# Schematic.net
KiCad netlist of a schematic drawn in EasyEDA
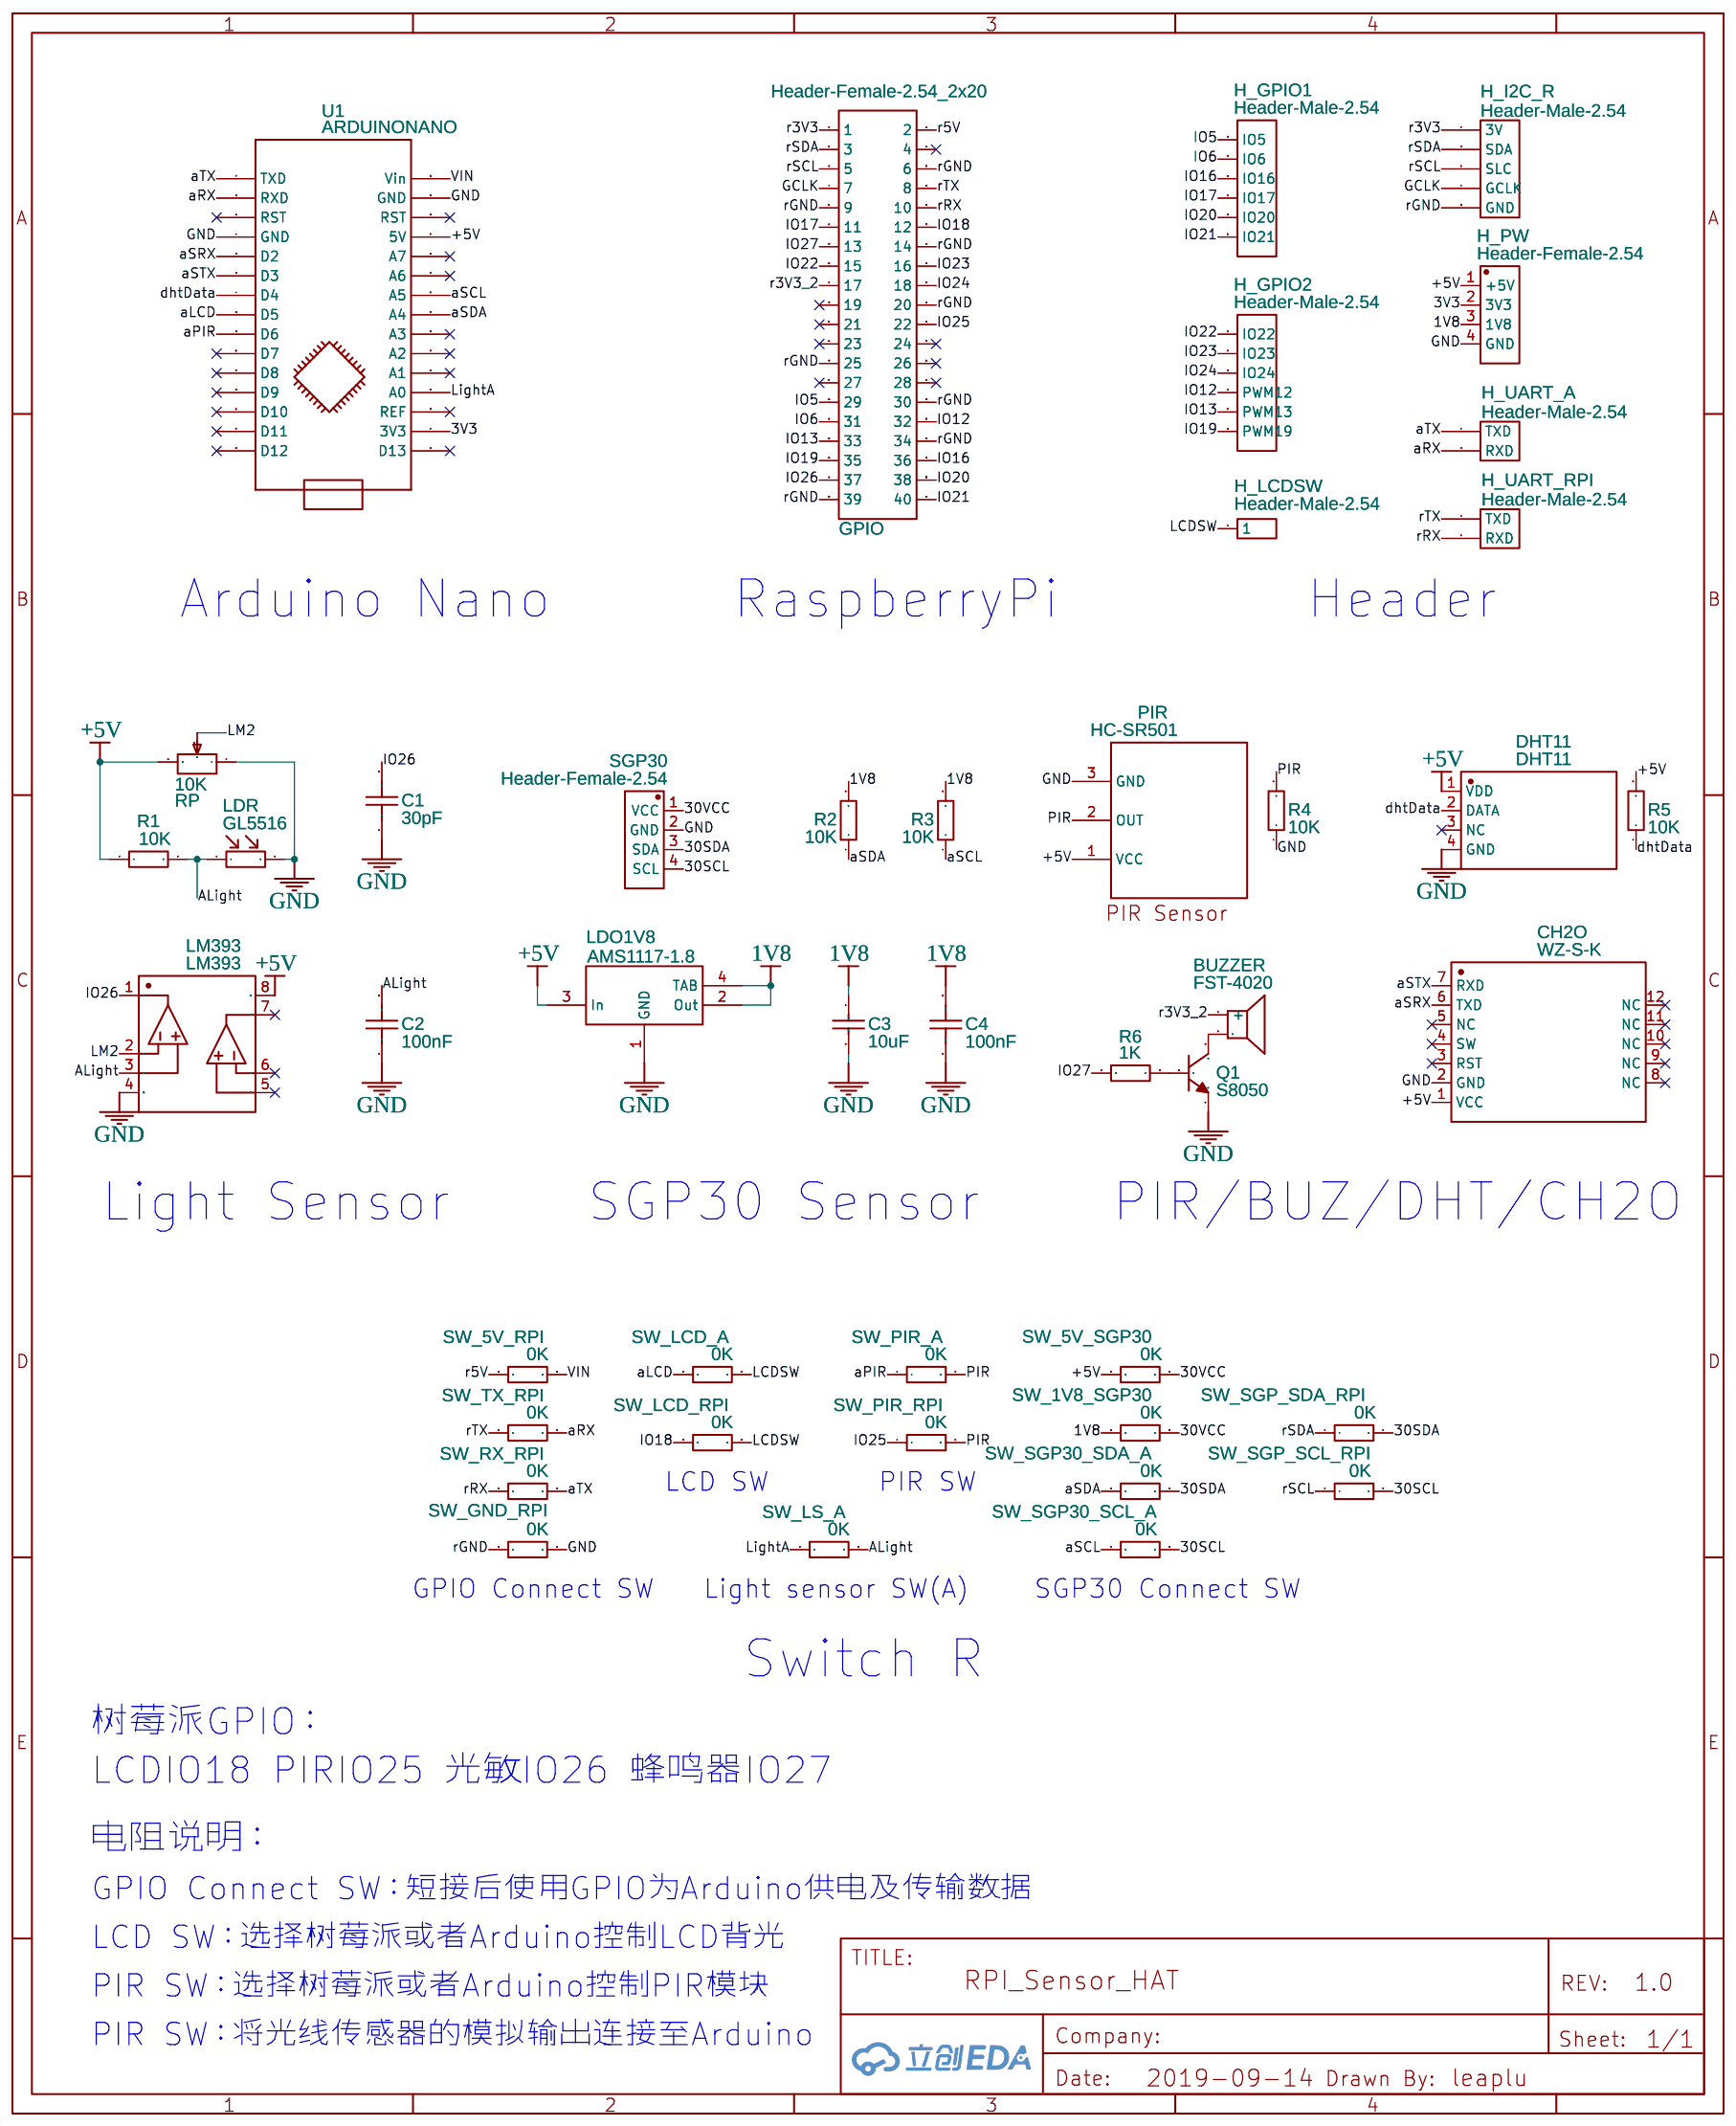
[diagram p0: schematic sheet]

(export (version "E")
  (design (tool "Eeschema 10.0.6"))
  (components
    (comp (ref "BUZZER")
      (value "FST-4020")
      (fields (field (name "BOM_Supplier Part") "C391027"))
      (libsource (lib "") (part "FST-4020"))
    )
    (comp (ref "C1")
      (value "30pF")
      (fields
        (field (name "BOM_Manufacturer Part") "CC0603GRNPO9BN300")
        (field (name "BOM_Supplier Part") "C327012")
      )
      (libsource (lib "") (part "CC0603GRNPO9BN300"))
    )
    (comp (ref "C2")
      (value "100nF")
      (fields
        (field (name "BOM_Manufacturer Part") "CC0603KRX7R0BB104")
        (field (name "BOM_Supplier Part") "C113803")
      )
      (libsource (lib "") (part "CC0603KRX7R0BB104"))
    )
    (comp (ref "C3")
      (value "10uF")
      (fields
        (field (name "BOM_Manufacturer Part") "CC0603KRX5R5BB106")
        (field (name "BOM_Supplier Part") "C109455")
      )
      (libsource (lib "") (part "CC0603KRX5R5BB106"))
    )
    (comp (ref "C4")
      (value "100nF")
      (fields
        (field (name "BOM_Manufacturer Part") "CC0603KRX7R0BB104")
        (field (name "BOM_Supplier Part") "C113803")
      )
      (libsource (lib "") (part "CC0603KRX7R0BB104"))
    )
    (comp (ref "CH2O") (value "WZ-S-K") (libsource (lib "") (part "Unknown_790_530")))
    (comp (ref "DHT11")
      (value "DHT11")
      (fields (field (name "BOM_Supplier Part") "C117051"))
      (libsource (lib "") (part "Unknown_780_415"))
    )
    (comp (ref "GPIO")
      (value "Header-Female-2.54_2x20")
      (fields
        (field (name "BOM_Manufacturer Part") "2.54mm 2*20PFemale header")
        (field (name "BOM_Supplier Part") "C50982")
      )
      (libsource (lib "") (part "Unknown_445_160"))
    )
    (comp (ref "H_GPIO1")
      (value "Header-Male-2.54")
      (fields
        (field (name "BOM_Manufacturer Part") "Header-Male-2.54_1x6")
        (field (name "BOM_Supplier Part") "C37208")
      )
      (libsource (lib "") (part "Header-Male-2.54_1x6_1"))
    )
    (comp (ref "H_GPIO2")
      (value "Header-Male-2.54")
      (fields
        (field (name "BOM_Manufacturer Part") "Header-Male-2.54_1x6")
        (field (name "BOM_Supplier Part") "C37208")
      )
      (libsource (lib "") (part "Header-Male-2.54_1x6"))
    )
    (comp (ref "H_I2C_R")
      (value "Header-Male-2.54")
      (fields
        (field (name "BOM_Manufacturer Part") "2.54mm 1*5P Header")
        (field (name "BOM_Supplier Part") "C50951")
      )
      (libsource (lib "") (part "Unknown_755_80"))
    )
    (comp (ref "H_LCDSW")
      (value "Header-Male-2.54")
      (fields
        (field (name "BOM_Manufacturer Part") "Header-Male-2.54_1x1")
        (field (name "BOM_Supplier Part") "C81276")
      )
      (libsource (lib "") (part "Header-Male-2.54_1x1"))
    )
    (comp (ref "H_PW")
      (value "Header-Female-2.54")
      (fields
        (field (name "BOM_Manufacturer Part") "Headers  Pins 1*4P")
        (field (name "BOM_Supplier Part") "C59481")
      )
      (libsource (lib "") (part "Unknown_760_155"))
    )
    (comp (ref "H_UART_A")
      (value "Header-Male-2.54")
      (fields
        (field (name "BOM_Manufacturer Part") "2.54mm 1*2P")
        (field (name "BOM_Supplier Part") "C36717")
      )
      (libsource (lib "") (part "Unknown_755_220"))
    )
    (comp (ref "H_UART_RPI")
      (value "Header-Male-2.54")
      (fields
        (field (name "BOM_Manufacturer Part") "2.54mm 1*2P")
        (field (name "BOM_Supplier Part") "C36717")
      )
      (libsource (lib "") (part "Unknown_755_265"))
    )
    (comp (ref "LDO1V8")
      (value "AMS1117-1.8")
      (fields (field (name "BOM_Supplier Part") "C6185"))
      (libsource (lib "") (part "Unknown_325_515"))
    )
    (comp (ref "LDR")
      (value "GL5516")
      (fields (field (name "BOM_Supplier Part") "C125626"))
      (libsource (lib "") (part "GL5516"))
    )
    (comp (ref "LM393")
      (value "LM393")
      (fields (field (name "BOM_Supplier Part") "C351428"))
      (libsource (lib "") (part "Unknown_95_525"))
    )
    (comp (ref "PIR") (value "HC-SR501") (libsource (lib "") (part "Unknown_605_415")))
    (comp (ref "Q1")
      (value "S8050")
      (fields (field (name "BOM_Supplier Part") "C181158"))
      (libsource (lib "") (part "Unknown_605_545"))
    )
    (comp (ref "R1")
      (value "10K")
      (fields
        (field (name "BOM_Manufacturer Part") "0603WAF1002T5E")
        (field (name "BOM_Supplier Part") "C25804")
      )
      (libsource (lib "") (part "RMC060310K5%N_4"))
    )
    (comp (ref "R2")
      (value "10K")
      (fields
        (field (name "BOM_Manufacturer Part") "0603WAF1002T5E")
        (field (name "BOM_Supplier Part") "C25804")
      )
      (libsource (lib "") (part "RMC060310K5%N_3"))
    )
    (comp (ref "R3")
      (value "10K")
      (fields
        (field (name "BOM_Manufacturer Part") "0603WAF1002T5E")
        (field (name "BOM_Supplier Part") "C25804")
      )
      (libsource (lib "") (part "RMC060310K5%N_3"))
    )
    (comp (ref "R4")
      (value "10K")
      (fields
        (field (name "BOM_Manufacturer Part") "0603WAF1002T5E")
        (field (name "BOM_Supplier Part") "C25804")
      )
      (libsource (lib "") (part "RMC060310K5%N_3"))
    )
    (comp (ref "R5")
      (value "10K")
      (fields
        (field (name "BOM_Manufacturer Part") "0603WAF1002T5E")
        (field (name "BOM_Supplier Part") "C25804")
      )
      (libsource (lib "") (part "RMC060310K5%N_3"))
    )
    (comp (ref "R6")
      (value "1K")
      (fields
        (field (name "BOM_Manufacturer Part") "RMC06031K5%N")
        (field (name "BOM_Supplier Part") "C269685")
      )
      (libsource (lib "") (part "RMC06031K5%N"))
    )
    (comp (ref "RP")
      (value "10K")
      (fields (field (name "BOM_Manufacturer Part") "3362P-1-103") (field (name "BOM_Supplier Part") "C5047"))
      (libsource (lib "") (part "3362P-1-103"))
    )
    (comp (ref "SGP30")
      (value "Header-Female-2.54")
      (fields
        (field (name "BOM_Manufacturer Part") "Headers  Pins 1*4P")
        (field (name "BOM_Supplier Part") "C59481")
      )
      (libsource (lib "") (part "Unknown_330_425"))
    )
    (comp (ref "SW_1V8_SGP30")
      (value "0K")
      (fields
        (field (name "BOM_Manufacturer Part") "0603WAF1002T5E")
        (field (name "BOM_Supplier Part") "C25804")
      )
      (libsource (lib "") (part "RMC060310K5%N_2"))
    )
    (comp (ref "SW_5V_RPI")
      (value "0K")
      (fields
        (field (name "BOM_Manufacturer Part") "0603WAF5101T5E")
        (field (name "BOM_Supplier Part") "C23186")
      )
      (libsource (lib "") (part "RMC06035.1K5%N_3"))
    )
    (comp (ref "SW_5V_SGP30")
      (value "0K")
      (fields
        (field (name "BOM_Manufacturer Part") "0603WAF1002T5E")
        (field (name "BOM_Supplier Part") "C25804")
      )
      (libsource (lib "") (part "RMC060310K5%N_6"))
    )
    (comp (ref "SW_GND_RPI")
      (value "0K")
      (fields
        (field (name "BOM_Manufacturer Part") "0603WAF5101T5E")
        (field (name "BOM_Supplier Part") "C23186")
      )
      (libsource (lib "") (part "RMC06035.1K5%N_5"))
    )
    (comp (ref "SW_LCD_A")
      (value "0K")
      (fields
        (field (name "BOM_Manufacturer Part") "0603WAF5101T5E")
        (field (name "BOM_Supplier Part") "C23186")
      )
      (libsource (lib "") (part "RMC06035.1K5%N_7"))
    )
    (comp (ref "SW_LCD_RPI")
      (value "0K")
      (fields
        (field (name "BOM_Manufacturer Part") "0603WAF5101T5E")
        (field (name "BOM_Supplier Part") "C23186")
      )
      (libsource (lib "") (part "RMC06035.1K5%N_1"))
    )
    (comp (ref "SW_LS_A")
      (value "0K")
      (fields
        (field (name "BOM_Manufacturer Part") "0603WAF5101T5E")
        (field (name "BOM_Supplier Part") "C23186")
      )
      (libsource (lib "") (part "RMC06035.1K5%N_4"))
    )
    (comp (ref "SW_PIR_A")
      (value "0K")
      (fields
        (field (name "BOM_Manufacturer Part") "0603WAF5101T5E")
        (field (name "BOM_Supplier Part") "C23186")
      )
      (libsource (lib "") (part "RMC06035.1K5%N_2"))
    )
    (comp (ref "SW_PIR_RPI")
      (value "0K")
      (fields
        (field (name "BOM_Manufacturer Part") "0603WAF5101T5E")
        (field (name "BOM_Supplier Part") "C23186")
      )
      (libsource (lib "") (part "RMC06035.1K5%N_6"))
    )
    (comp (ref "SW_RX_RPI")
      (value "0K")
      (fields
        (field (name "BOM_Manufacturer Part") "0603WAF5101T5E")
        (field (name "BOM_Supplier Part") "C23186")
      )
      (libsource (lib "") (part "RMC06035.1K5%N_8"))
    )
    (comp (ref "SW_SGP30_SCL_A")
      (value "0K")
      (fields
        (field (name "BOM_Manufacturer Part") "0603WAF1002T5E")
        (field (name "BOM_Supplier Part") "C25804")
      )
      (libsource (lib "") (part "RMC060310K5%N"))
    )
    (comp (ref "SW_SGP30_SDA_A")
      (value "0K")
      (fields
        (field (name "BOM_Manufacturer Part") "0603WAF1002T5E")
        (field (name "BOM_Supplier Part") "C25804")
      )
      (libsource (lib "") (part "RMC060310K5%N_1"))
    )
    (comp (ref "SW_SGP_SCL_RPI")
      (value "0K")
      (fields
        (field (name "BOM_Manufacturer Part") "0603WAF1002T5E")
        (field (name "BOM_Supplier Part") "C25804")
      )
      (libsource (lib "") (part "RMC060310K5%N_5"))
    )
    (comp (ref "SW_SGP_SDA_RPI")
      (value "0K")
      (fields
        (field (name "BOM_Manufacturer Part") "0603WAF1002T5E")
        (field (name "BOM_Supplier Part") "C25804")
      )
      (libsource (lib "") (part "RMC060310K5%N_7"))
    )
    (comp (ref "SW_TX_RPI")
      (value "0K")
      (fields
        (field (name "BOM_Manufacturer Part") "0603WAF5101T5E")
        (field (name "BOM_Supplier Part") "C23186")
      )
      (libsource (lib "") (part "RMC06035.1K5%N"))
    )
    (comp (ref "U1")
      (value "ARDUINONANO")
      (fields (field (name "BOM_Manufacturer Part") "ArduinoNano"))
      (libsource (lib "") (part "ARDUINONANO COPY"))
    )
  )
  (nets
    (net (code "1") (name "+5V") (class "Default")
      (node (ref "CH2O") (pin "1") (pinfunction "VCC_1") (pintype "unspecified"))
      (node (ref "DHT11") (pin "1") (pinfunction "VDD_1") (pintype "unspecified"))
      (node (ref "H_PW") (pin "1") (pinfunction "+5V_1") (pintype "unspecified"))
      (node (ref "LDO1V8") (pin "3") (pinfunction "In_3") (pintype "unspecified"))
      (node (ref "LM393") (pin "8") (pinfunction "VDD_8") (pintype "unspecified"))
      (node (ref "PIR") (pin "1") (pinfunction "VCC_1") (pintype "unspecified"))
      (node (ref "R1") (pin "1") (pinfunction "1_1") (pintype "unspecified"))
      (node (ref "R5") (pin "2") (pinfunction "2_2") (pintype "unspecified"))
      (node (ref "RP") (pin "3") (pinfunction "3_3") (pintype "input"))
      (node (ref "SW_5V_SGP30") (pin "1") (pinfunction "1_1") (pintype "unspecified"))
      (node (ref "U1") (pin "27") (pinfunction "5V_27") (pintype "unspecified"))
    )
    (net (code "2") (name "/3V3") (class "Default")
      (node (ref "H_PW") (pin "2") (pinfunction "3V3_2") (pintype "unspecified"))
      (node (ref "U1") (pin "17") (pinfunction "3V3_17") (pintype "unspecified"))
    )
    (net (code "3") (name "/30SCL") (class "Default")
      (node (ref "SGP30") (pin "4") (pinfunction "SCL_4") (pintype "unspecified"))
      (node (ref "SW_SGP30_SCL_A") (pin "2") (pinfunction "2_2") (pintype "unspecified"))
      (node (ref "SW_SGP_SCL_RPI") (pin "2") (pinfunction "2_2") (pintype "unspecified"))
    )
    (net (code "4") (name "/30SDA") (class "Default")
      (node (ref "SGP30") (pin "3") (pinfunction "SDA_3") (pintype "unspecified"))
      (node (ref "SW_SGP30_SDA_A") (pin "2") (pinfunction "2_2") (pintype "unspecified"))
      (node (ref "SW_SGP_SDA_RPI") (pin "2") (pinfunction "2_2") (pintype "unspecified"))
    )
    (net (code "5") (name "/30VCC") (class "Default")
      (node (ref "SGP30") (pin "1") (pinfunction "VCC_1") (pintype "unspecified"))
      (node (ref "SW_1V8_SGP30") (pin "2") (pinfunction "2_2") (pintype "unspecified"))
      (node (ref "SW_5V_SGP30") (pin "2") (pinfunction "2_2") (pintype "unspecified"))
    )
    (net (code "6") (name "/ALight") (class "Default")
      (node (ref "C2") (pin "2") (pinfunction "2_2") (pintype "unspecified"))
      (node (ref "LDR") (pin "1") (pinfunction "1_1") (pintype "input"))
      (node (ref "LM393") (pin "3") (pinfunction "3_3") (pintype "unspecified"))
      (node (ref "R1") (pin "2") (pinfunction "2_2") (pintype "unspecified"))
      (node (ref "SW_LS_A") (pin "2") (pinfunction "2_2") (pintype "unspecified"))
    )
    (net (code "7") (name "/GCLK") (class "Default")
      (node (ref "GPIO") (pin "7") (pinfunction "7_7") (pintype "input"))
      (node (ref "H_I2C_R") (pin "4") (pinfunction "GCLK_4") (pintype "input"))
    )
    (net (code "8") (name "/IO5") (class "Default")
      (node (ref "GPIO") (pin "29") (pinfunction "29_29") (pintype "input"))
      (node (ref "H_GPIO1") (pin "1") (pinfunction "IO5_1") (pintype "input"))
    )
    (net (code "9") (name "/IO6") (class "Default")
      (node (ref "GPIO") (pin "31") (pinfunction "31_31") (pintype "input"))
      (node (ref "H_GPIO1") (pin "2") (pinfunction "IO6_2") (pintype "input"))
    )
    (net (code "10") (name "/IO12") (class "Default")
      (node (ref "GPIO") (pin "32") (pinfunction "32_32") (pintype "input"))
      (node (ref "H_GPIO2") (pin "4") (pinfunction "PWM12_4") (pintype "input"))
    )
    (net (code "11") (name "/IO13") (class "Default")
      (node (ref "GPIO") (pin "33") (pinfunction "33_33") (pintype "input"))
      (node (ref "H_GPIO2") (pin "5") (pinfunction "PWM13_5") (pintype "input"))
    )
    (net (code "12") (name "/IO16") (class "Default")
      (node (ref "GPIO") (pin "36") (pinfunction "36_36") (pintype "input"))
      (node (ref "H_GPIO1") (pin "3") (pinfunction "IO16_3") (pintype "input"))
    )
    (net (code "13") (name "/IO17") (class "Default")
      (node (ref "GPIO") (pin "11") (pinfunction "11_11") (pintype "input"))
      (node (ref "H_GPIO1") (pin "4") (pinfunction "IO17_4") (pintype "input"))
    )
    (net (code "14") (name "/IO18") (class "Default")
      (node (ref "GPIO") (pin "12") (pinfunction "12_12") (pintype "input"))
      (node (ref "SW_LCD_RPI") (pin "1") (pinfunction "1_1") (pintype "unspecified"))
    )
    (net (code "15") (name "/IO19") (class "Default")
      (node (ref "GPIO") (pin "35") (pinfunction "35_35") (pintype "input"))
      (node (ref "H_GPIO2") (pin "6") (pinfunction "PWM19_6") (pintype "input"))
    )
    (net (code "16") (name "/IO20") (class "Default")
      (node (ref "GPIO") (pin "38") (pinfunction "38_38") (pintype "input"))
      (node (ref "H_GPIO1") (pin "5") (pinfunction "IO20_5") (pintype "input"))
    )
    (net (code "17") (name "/IO21") (class "Default")
      (node (ref "GPIO") (pin "40") (pinfunction "40_40") (pintype "input"))
      (node (ref "H_GPIO1") (pin "6") (pinfunction "IO21_6") (pintype "input"))
    )
    (net (code "18") (name "/IO22") (class "Default")
      (node (ref "GPIO") (pin "15") (pinfunction "15_15") (pintype "input"))
      (node (ref "H_GPIO2") (pin "1") (pinfunction "IO22_1") (pintype "input"))
    )
    (net (code "19") (name "/IO23") (class "Default")
      (node (ref "GPIO") (pin "16") (pinfunction "16_16") (pintype "input"))
      (node (ref "H_GPIO2") (pin "2") (pinfunction "IO23_2") (pintype "input"))
    )
    (net (code "20") (name "/IO24") (class "Default")
      (node (ref "GPIO") (pin "18") (pinfunction "18_18") (pintype "input"))
      (node (ref "H_GPIO2") (pin "3") (pinfunction "IO24_3") (pintype "input"))
    )
    (net (code "21") (name "/IO25") (class "Default")
      (node (ref "GPIO") (pin "22") (pinfunction "22_22") (pintype "input"))
      (node (ref "SW_PIR_RPI") (pin "1") (pinfunction "1_1") (pintype "unspecified"))
    )
    (net (code "22") (name "/IO26") (class "Default")
      (node (ref "C1") (pin "2") (pinfunction "2_2") (pintype "unspecified"))
      (node (ref "GPIO") (pin "37") (pinfunction "37_37") (pintype "input"))
      (node (ref "LM393") (pin "1") (pinfunction "1_1") (pintype "unspecified"))
    )
    (net (code "23") (name "/IO27") (class "Default")
      (node (ref "GPIO") (pin "13") (pinfunction "13_13") (pintype "input"))
      (node (ref "R6") (pin "1") (pinfunction "1_1") (pintype "unspecified"))
    )
    (net (code "24") (name "/LCDSW") (class "Default")
      (node (ref "H_LCDSW") (pin "1") (pinfunction "1_1") (pintype "input"))
      (node (ref "SW_LCD_A") (pin "2") (pinfunction "2_2") (pintype "unspecified"))
      (node (ref "SW_LCD_RPI") (pin "2") (pinfunction "2_2") (pintype "unspecified"))
    )
    (net (code "25") (name "/LM2") (class "Default")
      (node (ref "LM393") (pin "2") (pinfunction "2_2") (pintype "unspecified"))
      (node (ref "RP") (pin "2") (pinfunction "2_2") (pintype "input"))
    )
    (net (code "26") (name "/LightA") (class "Default")
      (node (ref "SW_LS_A") (pin "1") (pinfunction "1_1") (pintype "unspecified"))
      (node (ref "U1") (pin "19") (pinfunction "A0_19") (pintype "unspecified"))
    )
    (net (code "27") (name "/PIR") (class "Default")
      (node (ref "PIR") (pin "2") (pinfunction "OUT_2") (pintype "unspecified"))
      (node (ref "R4") (pin "2") (pinfunction "2_2") (pintype "unspecified"))
      (node (ref "SW_PIR_A") (pin "2") (pinfunction "2_2") (pintype "unspecified"))
      (node (ref "SW_PIR_RPI") (pin "2") (pinfunction "2_2") (pintype "unspecified"))
    )
    (net (code "28") (name "/VIN") (class "Default")
      (node (ref "SW_5V_RPI") (pin "2") (pinfunction "2_2") (pintype "unspecified"))
      (node (ref "U1") (pin "30") (pinfunction "Vin_30") (pintype "unspecified"))
    )
    (net (code "29") (name "/aLCD") (class "Default")
      (node (ref "SW_LCD_A") (pin "1") (pinfunction "1_1") (pintype "unspecified"))
      (node (ref "U1") (pin "8") (pinfunction "D5_8") (pintype "unspecified"))
    )
    (net (code "30") (name "/aPIR") (class "Default")
      (node (ref "SW_PIR_A") (pin "1") (pinfunction "1_1") (pintype "unspecified"))
      (node (ref "U1") (pin "9") (pinfunction "D6_9") (pintype "unspecified"))
    )
    (net (code "31") (name "/aRX") (class "Default")
      (node (ref "H_UART_A") (pin "2") (pinfunction "RXD_2") (pintype "input"))
      (node (ref "SW_TX_RPI") (pin "2") (pinfunction "2_2") (pintype "unspecified"))
      (node (ref "U1") (pin "2") (pinfunction "RXD_2") (pintype "unspecified"))
    )
    (net (code "32") (name "/aSCL") (class "Default")
      (node (ref "R3") (pin "1") (pinfunction "1_1") (pintype "unspecified"))
      (node (ref "SW_SGP30_SCL_A") (pin "1") (pinfunction "1_1") (pintype "unspecified"))
      (node (ref "U1") (pin "24") (pinfunction "A5_24") (pintype "unspecified"))
    )
    (net (code "33") (name "/aSDA") (class "Default")
      (node (ref "R2") (pin "1") (pinfunction "1_1") (pintype "unspecified"))
      (node (ref "SW_SGP30_SDA_A") (pin "1") (pinfunction "1_1") (pintype "unspecified"))
      (node (ref "U1") (pin "23") (pinfunction "A4_23") (pintype "unspecified"))
    )
    (net (code "34") (name "/aSRX") (class "Default")
      (node (ref "CH2O") (pin "6") (pinfunction "TXD_6") (pintype "unspecified"))
      (node (ref "U1") (pin "5") (pinfunction "D2_5") (pintype "unspecified"))
    )
    (net (code "35") (name "/aSTX") (class "Default")
      (node (ref "CH2O") (pin "7") (pinfunction "RXD_7") (pintype "unspecified"))
      (node (ref "U1") (pin "6") (pinfunction "D3_6") (pintype "unspecified"))
    )
    (net (code "36") (name "/aTX") (class "Default")
      (node (ref "H_UART_A") (pin "1") (pinfunction "TXD_1") (pintype "input"))
      (node (ref "SW_RX_RPI") (pin "2") (pinfunction "2_2") (pintype "unspecified"))
      (node (ref "U1") (pin "1") (pinfunction "TXD_1") (pintype "unspecified"))
    )
    (net (code "37") (name "/dhtData") (class "Default")
      (node (ref "DHT11") (pin "2") (pinfunction "DATA_2") (pintype "unspecified"))
      (node (ref "R5") (pin "1") (pinfunction "1_1") (pintype "unspecified"))
      (node (ref "U1") (pin "7") (pinfunction "D4_7") (pintype "unspecified"))
    )
    (net (code "38") (name "/r3V3") (class "Default")
      (node (ref "GPIO") (pin "1") (pinfunction "1_1") (pintype "input"))
      (node (ref "H_I2C_R") (pin "1") (pinfunction "3V_1") (pintype "input"))
    )
    (net (code "39") (name "/r3V3_2") (class "Default")
      (node (ref "BUZZER") (pin "1") (pinfunction "+_1") (pintype "unspecified"))
      (node (ref "GPIO") (pin "17") (pinfunction "17_17") (pintype "input"))
    )
    (net (code "40") (name "/r5V") (class "Default")
      (node (ref "GPIO") (pin "2") (pinfunction "2_2") (pintype "input"))
      (node (ref "SW_5V_RPI") (pin "1") (pinfunction "1_1") (pintype "unspecified"))
    )
    (net (code "41") (name "/rGND") (class "Default")
      (node (ref "GPIO") (pin "14") (pinfunction "14_14") (pintype "input"))
      (node (ref "GPIO") (pin "20") (pinfunction "20_20") (pintype "input"))
      (node (ref "GPIO") (pin "25") (pinfunction "25_25") (pintype "input"))
      (node (ref "GPIO") (pin "30") (pinfunction "30_30") (pintype "input"))
      (node (ref "GPIO") (pin "34") (pinfunction "34_34") (pintype "input"))
      (node (ref "GPIO") (pin "39") (pinfunction "39_39") (pintype "input"))
      (node (ref "GPIO") (pin "6") (pinfunction "6_6") (pintype "input"))
      (node (ref "GPIO") (pin "9") (pinfunction "9_9") (pintype "input"))
      (node (ref "H_I2C_R") (pin "5") (pinfunction "GND_5") (pintype "input"))
      (node (ref "SW_GND_RPI") (pin "1") (pinfunction "1_1") (pintype "unspecified"))
    )
    (net (code "42") (name "/rRX") (class "Default")
      (node (ref "GPIO") (pin "10") (pinfunction "10_10") (pintype "input"))
      (node (ref "H_UART_RPI") (pin "2") (pinfunction "RXD_2") (pintype "input"))
      (node (ref "SW_RX_RPI") (pin "1") (pinfunction "1_1") (pintype "unspecified"))
    )
    (net (code "43") (name "/rSCL") (class "Default")
      (node (ref "GPIO") (pin "5") (pinfunction "5_5") (pintype "input"))
      (node (ref "H_I2C_R") (pin "3") (pinfunction "SLC_3") (pintype "input"))
      (node (ref "SW_SGP_SCL_RPI") (pin "1") (pinfunction "1_1") (pintype "unspecified"))
    )
    (net (code "44") (name "/rSDA") (class "Default")
      (node (ref "GPIO") (pin "3") (pinfunction "3_3") (pintype "input"))
      (node (ref "H_I2C_R") (pin "2") (pinfunction "SDA_2") (pintype "input"))
      (node (ref "SW_SGP_SDA_RPI") (pin "1") (pinfunction "1_1") (pintype "unspecified"))
    )
    (net (code "45") (name "/rTX") (class "Default")
      (node (ref "GPIO") (pin "8") (pinfunction "8_8") (pintype "input"))
      (node (ref "H_UART_RPI") (pin "1") (pinfunction "TXD_1") (pintype "input"))
      (node (ref "SW_TX_RPI") (pin "1") (pinfunction "1_1") (pintype "unspecified"))
    )
    (net (code "46") (name "1V8") (class "Default")
      (node (ref "C3") (pin "1") (pinfunction "1_1") (pintype "input"))
      (node (ref "C4") (pin "2") (pinfunction "2_2") (pintype "unspecified"))
      (node (ref "H_PW") (pin "3") (pinfunction "1V8_3") (pintype "unspecified"))
      (node (ref "LDO1V8") (pin "2") (pinfunction "Out_2") (pintype "unspecified"))
      (node (ref "LDO1V8") (pin "4") (pinfunction "TAB_4") (pintype "unspecified"))
      (node (ref "R2") (pin "2") (pinfunction "2_2") (pintype "unspecified"))
      (node (ref "R3") (pin "2") (pinfunction "2_2") (pintype "unspecified"))
      (node (ref "SW_1V8_SGP30") (pin "1") (pinfunction "1_1") (pintype "unspecified"))
    )
    (net (code "47") (name "GND") (class "Default")
      (node (ref "C1") (pin "1") (pinfunction "1_1") (pintype "unspecified"))
      (node (ref "C2") (pin "1") (pinfunction "1_1") (pintype "unspecified"))
      (node (ref "C3") (pin "2") (pinfunction "2_2") (pintype "input"))
      (node (ref "C4") (pin "1") (pinfunction "1_1") (pintype "unspecified"))
      (node (ref "CH2O") (pin "2") (pinfunction "GND_2") (pintype "unspecified"))
      (node (ref "DHT11") (pin "4") (pinfunction "GND_4") (pintype "unspecified"))
      (node (ref "H_PW") (pin "4") (pinfunction "GND_4") (pintype "unspecified"))
      (node (ref "LDO1V8") (pin "1") (pinfunction "GND_1") (pintype "unspecified"))
      (node (ref "LDR") (pin "2") (pinfunction "2_2") (pintype "input"))
      (node (ref "LM393") (pin "4") (pinfunction "GND_4") (pintype "unspecified"))
      (node (ref "PIR") (pin "3") (pinfunction "GND_3") (pintype "unspecified"))
      (node (ref "Q1") (pin "2") (pinfunction "2_2") (pintype "input"))
      (node (ref "R4") (pin "1") (pinfunction "1_1") (pintype "unspecified"))
      (node (ref "RP") (pin "1") (pinfunction "1_1") (pintype "input"))
      (node (ref "SGP30") (pin "2") (pinfunction "GND_2") (pintype "unspecified"))
      (node (ref "SW_GND_RPI") (pin "2") (pinfunction "2_2") (pintype "unspecified"))
      (node (ref "U1") (pin "29") (pinfunction "GND_29") (pintype "unspecified"))
      (node (ref "U1") (pin "4") (pinfunction "GND_4") (pintype "unspecified"))
    )
    (net (code "48") (name "Net-(BUZZER-Pad2)") (class "Default")
      (node (ref "BUZZER") (pin "2") (pinfunction "2_2") (pintype "unspecified"))
      (node (ref "Q1") (pin "3") (pinfunction "3_3") (pintype "input"))
    )
    (net (code "49") (name "Net-(Q1-Pad1)") (class "Default")
      (node (ref "Q1") (pin "1") (pinfunction "1_1") (pintype "input"))
      (node (ref "R6") (pin "2") (pinfunction "2_2") (pintype "unspecified"))
    )
    (net (code "50") (name "unconnected-(CH2O-NC-Pad5)") (class "Default")
      (node (ref "CH2O") (pin "5") (pinfunction "NC_5") (pintype "unspecified+no_connect"))
    )
    (net (code "51") (name "unconnected-(CH2O-NC-Pad8)") (class "Default")
      (node (ref "CH2O") (pin "8") (pinfunction "NC_8") (pintype "unspecified+no_connect"))
    )
    (net (code "52") (name "unconnected-(CH2O-NC-Pad9)") (class "Default")
      (node (ref "CH2O") (pin "9") (pinfunction "NC_9") (pintype "unspecified+no_connect"))
    )
    (net (code "53") (name "unconnected-(CH2O-NC-Pad10)") (class "Default")
      (node (ref "CH2O") (pin "10") (pinfunction "NC_10") (pintype "unspecified+no_connect"))
    )
    (net (code "54") (name "unconnected-(CH2O-NC-Pad11)") (class "Default")
      (node (ref "CH2O") (pin "11") (pinfunction "NC_11") (pintype "unspecified+no_connect"))
    )
    (net (code "55") (name "unconnected-(CH2O-NC-Pad12)") (class "Default")
      (node (ref "CH2O") (pin "12") (pinfunction "NC_12") (pintype "unspecified+no_connect"))
    )
    (net (code "56") (name "unconnected-(CH2O-RST-Pad3)") (class "Default")
      (node (ref "CH2O") (pin "3") (pinfunction "RST_3") (pintype "unspecified+no_connect"))
    )
    (net (code "57") (name "unconnected-(CH2O-SW-Pad4)") (class "Default")
      (node (ref "CH2O") (pin "4") (pinfunction "SW_4") (pintype "unspecified+no_connect"))
    )
    (net (code "58") (name "unconnected-(DHT11-NC-Pad3)") (class "Default")
      (node (ref "DHT11") (pin "3") (pinfunction "NC_3") (pintype "unspecified+no_connect"))
    )
    (net (code "59") (name "unconnected-(GPIO-Pad4)") (class "Default")
      (node (ref "GPIO") (pin "4") (pinfunction "4_4") (pintype "input+no_connect"))
    )
    (net (code "60") (name "unconnected-(GPIO-Pad19)") (class "Default")
      (node (ref "GPIO") (pin "19") (pinfunction "19_19") (pintype "input+no_connect"))
    )
    (net (code "61") (name "unconnected-(GPIO-Pad21)") (class "Default")
      (node (ref "GPIO") (pin "21") (pinfunction "21_21") (pintype "input+no_connect"))
    )
    (net (code "62") (name "unconnected-(GPIO-Pad23)") (class "Default")
      (node (ref "GPIO") (pin "23") (pinfunction "23_23") (pintype "input+no_connect"))
    )
    (net (code "63") (name "unconnected-(GPIO-Pad24)") (class "Default")
      (node (ref "GPIO") (pin "24") (pinfunction "24_24") (pintype "input+no_connect"))
    )
    (net (code "64") (name "unconnected-(GPIO-Pad26)") (class "Default")
      (node (ref "GPIO") (pin "26") (pinfunction "26_26") (pintype "input+no_connect"))
    )
    (net (code "65") (name "unconnected-(GPIO-Pad27)") (class "Default")
      (node (ref "GPIO") (pin "27") (pinfunction "27_27") (pintype "input+no_connect"))
    )
    (net (code "66") (name "unconnected-(GPIO-Pad28)") (class "Default")
      (node (ref "GPIO") (pin "28") (pinfunction "28_28") (pintype "input+no_connect"))
    )
    (net (code "67") (name "unconnected-(LM393-Pad5)") (class "Default")
      (node (ref "LM393") (pin "5") (pinfunction "5_5") (pintype "unspecified+no_connect"))
    )
    (net (code "68") (name "unconnected-(LM393-Pad6)") (class "Default")
      (node (ref "LM393") (pin "6") (pinfunction "6_6") (pintype "unspecified+no_connect"))
    )
    (net (code "69") (name "unconnected-(LM393-Pad7)") (class "Default")
      (node (ref "LM393") (pin "7") (pinfunction "7_7") (pintype "unspecified+no_connect"))
    )
    (net (code "70") (name "unconnected-(U1-A1-Pad20)") (class "Default")
      (node (ref "U1") (pin "20") (pinfunction "A1_20") (pintype "unspecified+no_connect"))
    )
    (net (code "71") (name "unconnected-(U1-A2-Pad21)") (class "Default")
      (node (ref "U1") (pin "21") (pinfunction "A2_21") (pintype "unspecified+no_connect"))
    )
    (net (code "72") (name "unconnected-(U1-A3-Pad22)") (class "Default")
      (node (ref "U1") (pin "22") (pinfunction "A3_22") (pintype "unspecified+no_connect"))
    )
    (net (code "73") (name "unconnected-(U1-A6-Pad25)") (class "Default")
      (node (ref "U1") (pin "25") (pinfunction "A6_25") (pintype "unspecified+no_connect"))
    )
    (net (code "74") (name "unconnected-(U1-A7-Pad26)") (class "Default")
      (node (ref "U1") (pin "26") (pinfunction "A7_26") (pintype "unspecified+no_connect"))
    )
    (net (code "75") (name "unconnected-(U1-D7-Pad10)") (class "Default")
      (node (ref "U1") (pin "10") (pinfunction "D7_10") (pintype "unspecified+no_connect"))
    )
    (net (code "76") (name "unconnected-(U1-D8-Pad11)") (class "Default")
      (node (ref "U1") (pin "11") (pinfunction "D8_11") (pintype "unspecified+no_connect"))
    )
    (net (code "77") (name "unconnected-(U1-D9-Pad12)") (class "Default")
      (node (ref "U1") (pin "12") (pinfunction "D9_12") (pintype "unspecified+no_connect"))
    )
    (net (code "78") (name "unconnected-(U1-D10-Pad13)") (class "Default")
      (node (ref "U1") (pin "13") (pinfunction "D10_13") (pintype "unspecified+no_connect"))
    )
    (net (code "79") (name "unconnected-(U1-D11-Pad14)") (class "Default")
      (node (ref "U1") (pin "14") (pinfunction "D11_14") (pintype "unspecified+no_connect"))
    )
    (net (code "80") (name "unconnected-(U1-D12-Pad15)") (class "Default")
      (node (ref "U1") (pin "15") (pinfunction "D12_15") (pintype "unspecified+no_connect"))
    )
    (net (code "81") (name "unconnected-(U1-D13-Pad16)") (class "Default")
      (node (ref "U1") (pin "16") (pinfunction "D13_16") (pintype "unspecified+no_connect"))
    )
    (net (code "82") (name "unconnected-(U1-REF-Pad18)") (class "Default")
      (node (ref "U1") (pin "18") (pinfunction "REF_18") (pintype "unspecified+no_connect"))
    )
    (net (code "83") (name "unconnected-(U1-RST-Pad3)") (class "Default")
      (node (ref "U1") (pin "3") (pinfunction "RST_3") (pintype "unspecified+no_connect"))
    )
    (net (code "84") (name "unconnected-(U1-RST-Pad28)") (class "Default")
      (node (ref "U1") (pin "28") (pinfunction "RST_28") (pintype "unspecified+no_connect"))
    )
  )
)
